# femto.net
KiCad netlist of a schematic drawn in EAGLE
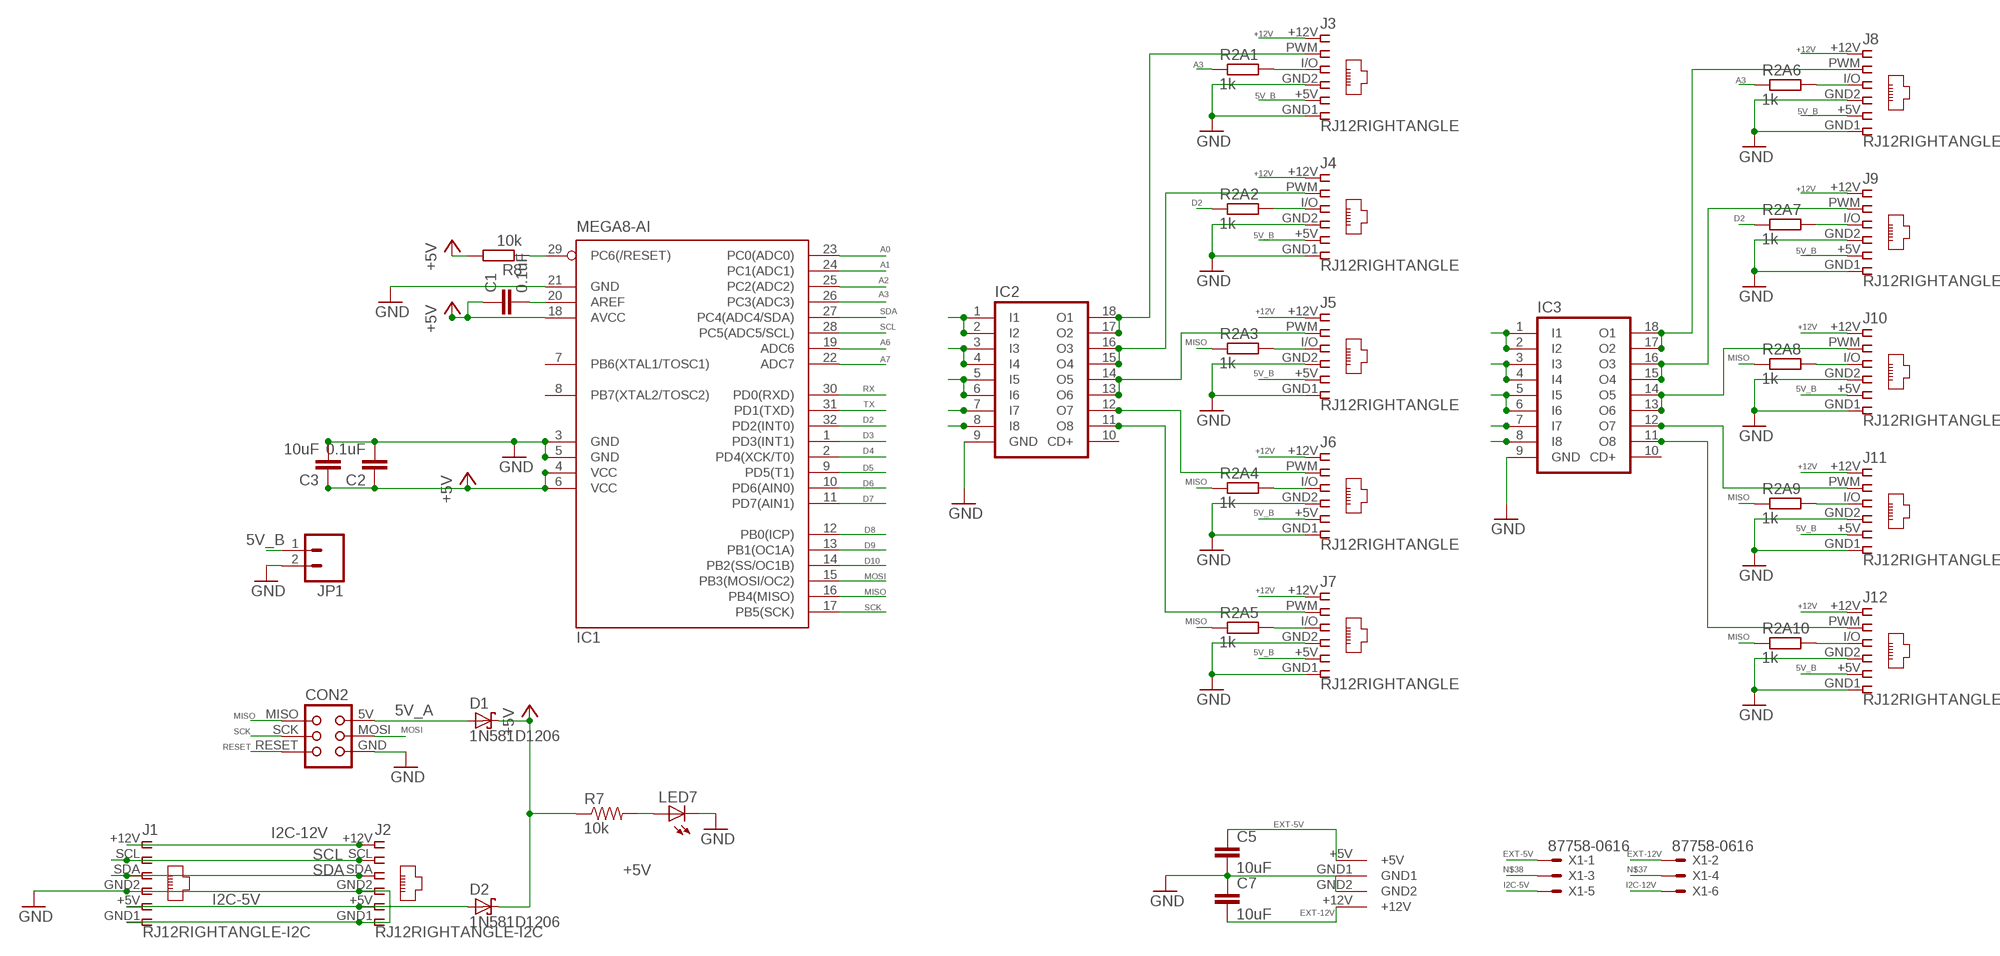
[diagram p0: schematic, sheet 1]

(export (version "E")
  (design (tool "Eeschema 10.0.6"))
  (components
    (comp (ref "C1")
      (value "0.1uF")
      (footprint "eagle-import:C1206")
      (libsource (lib "eagle-import") (part "resistor_C-EUC1206"))
    )
    (comp (ref "C2")
      (value "0.1uF")
      (footprint "eagle-import:C1206")
      (libsource (lib "eagle-import") (part "resistor_C-EUC1206"))
    )
    (comp (ref "C3")
      (value "10uF")
      (footprint "eagle-import:C1206")
      (libsource (lib "eagle-import") (part "resistor_C-EUC1206"))
    )
    (comp (ref "C5")
      (value "10uF")
      (footprint "eagle-import:C1206")
      (libsource (lib "eagle-import") (part "C-EUC1206"))
    )
    (comp (ref "C7")
      (value "10uF")
      (footprint "eagle-import:C1206")
      (libsource (lib "eagle-import") (part "C-EUC1206"))
    )
    (comp (ref "CON2")
      (value "TINYISPTAG")
      (footprint "eagle-import:TC2030-MCP")
      (libsource (lib "eagle-import") (part "TINYISPTAG"))
    )
    (comp (ref "D1")
      (value "1N581D1206")
      (footprint "eagle-import:LED-1206")
      (libsource (lib "eagle-import") (part "1N581D1206"))
    )
    (comp (ref "D2")
      (value "1N581D1206")
      (footprint "eagle-import:LED-1206")
      (libsource (lib "eagle-import") (part "1N581D1206"))
    )
    (comp (ref "IC1")
      (value "MEGA8-AI")
      (footprint "eagle-import:TQFP32-08")
      (fields (field (name "MPN") "ATMEGA8-16AU"))
      (libsource (lib "eagle-import") (part "MEGA8-AI"))
    )
    (comp (ref "IC2")
      (value "ULN2803A")
      (footprint "eagle-import:SO18W")
      (libsource (lib "eagle-import") (part "ULN2803A"))
    )
    (comp (ref "IC3")
      (value "ULN2803A")
      (footprint "eagle-import:SO18W")
      (libsource (lib "eagle-import") (part "ULN2803A"))
    )
    (comp (ref "J1")
      (value "RJ12RIGHTANGLE-I2C")
      (footprint "eagle-import:RJ12-RIGHTANGLE-I2C")
      (libsource (lib "eagle-import") (part "RJ12RIGHTANGLE-I2C"))
    )
    (comp (ref "J2")
      (value "RJ12RIGHTANGLE-I2C")
      (footprint "eagle-import:RJ12-RIGHTANGLE-I2C")
      (libsource (lib "eagle-import") (part "RJ12RIGHTANGLE-I2C"))
    )
    (comp (ref "J3")
      (value "RJ12RIGHTANGLE")
      (footprint "eagle-import:RJ12-RIGHTANGLE")
      (libsource (lib "eagle-import") (part "RJ12RIGHTANGLE"))
    )
    (comp (ref "J4")
      (value "RJ12RIGHTANGLE")
      (footprint "eagle-import:RJ12-RIGHTANGLE")
      (libsource (lib "eagle-import") (part "RJ12RIGHTANGLE"))
    )
    (comp (ref "J5")
      (value "RJ12RIGHTANGLE")
      (footprint "eagle-import:RJ12-RIGHTANGLE")
      (libsource (lib "eagle-import") (part "RJ12RIGHTANGLE"))
    )
    (comp (ref "J6")
      (value "RJ12RIGHTANGLE")
      (footprint "eagle-import:RJ12-RIGHTANGLE")
      (libsource (lib "eagle-import") (part "RJ12RIGHTANGLE"))
    )
    (comp (ref "J7")
      (value "RJ12RIGHTANGLE")
      (footprint "eagle-import:RJ12-RIGHTANGLE")
      (libsource (lib "eagle-import") (part "RJ12RIGHTANGLE"))
    )
    (comp (ref "J8")
      (value "RJ12RIGHTANGLE")
      (footprint "eagle-import:RJ12-RIGHTANGLE")
      (libsource (lib "eagle-import") (part "RJ12RIGHTANGLE"))
    )
    (comp (ref "J9")
      (value "RJ12RIGHTANGLE")
      (footprint "eagle-import:RJ12-RIGHTANGLE")
      (libsource (lib "eagle-import") (part "RJ12RIGHTANGLE"))
    )
    (comp (ref "J10")
      (value "RJ12RIGHTANGLE")
      (footprint "eagle-import:RJ12-RIGHTANGLE")
      (libsource (lib "eagle-import") (part "RJ12RIGHTANGLE"))
    )
    (comp (ref "J11")
      (value "RJ12RIGHTANGLE")
      (footprint "eagle-import:RJ12-RIGHTANGLE")
      (libsource (lib "eagle-import") (part "RJ12RIGHTANGLE"))
    )
    (comp (ref "J12")
      (value "RJ12RIGHTANGLE")
      (footprint "eagle-import:RJ12-RIGHTANGLE")
      (libsource (lib "eagle-import") (part "RJ12RIGHTANGLE"))
    )
    (comp (ref "JP1")
      (value "M023.5MM")
      (footprint "eagle-import:SCREWTERMINAL-3.5MM-2")
      (libsource (lib "eagle-import") (part "M023.5MM"))
    )
    (comp (ref "LED7")
      (value "LEDCHIP-LED0603")
      (footprint "eagle-import:CHIP-LED0603")
      (libsource (lib "eagle-import") (part "LEDCHIP-LED0603"))
    )
    (comp (ref "R2A1")
      (value "1k")
      (footprint "eagle-import:M1206")
      (libsource (lib "eagle-import") (part "R-EU_M1206"))
    )
    (comp (ref "R2A2")
      (value "1k")
      (footprint "eagle-import:M1206")
      (libsource (lib "eagle-import") (part "R-EU_M1206"))
    )
    (comp (ref "R2A3")
      (value "1k")
      (footprint "eagle-import:M1206")
      (libsource (lib "eagle-import") (part "R-EU_M1206"))
    )
    (comp (ref "R2A4")
      (value "1k")
      (footprint "eagle-import:M1206")
      (libsource (lib "eagle-import") (part "R-EU_M1206"))
    )
    (comp (ref "R2A5")
      (value "1k")
      (footprint "eagle-import:M1206")
      (libsource (lib "eagle-import") (part "R-EU_M1206"))
    )
    (comp (ref "R2A6")
      (value "1k")
      (footprint "eagle-import:M1206")
      (libsource (lib "eagle-import") (part "R-EU_M1206"))
    )
    (comp (ref "R2A7")
      (value "1k")
      (footprint "eagle-import:M1206")
      (libsource (lib "eagle-import") (part "R-EU_M1206"))
    )
    (comp (ref "R2A8")
      (value "1k")
      (footprint "eagle-import:M1206")
      (libsource (lib "eagle-import") (part "R-EU_M1206"))
    )
    (comp (ref "R2A9")
      (value "1k")
      (footprint "eagle-import:M1206")
      (libsource (lib "eagle-import") (part "R-EU_M1206"))
    )
    (comp (ref "R2A10")
      (value "1k")
      (footprint "eagle-import:M1206")
      (libsource (lib "eagle-import") (part "R-EU_M1206"))
    )
    (comp (ref "R7")
      (value "10k")
      (footprint "eagle-import:0603-RES")
      (libsource (lib "eagle-import") (part "RESISTOR0603-RES"))
    )
    (comp (ref "R8")
      (value "10k")
      (footprint "eagle-import:M1206")
      (libsource (lib "eagle-import") (part "R-EU_M1206"))
    )
    (comp (ref "U$1")
      (value "KPJX-4S-S")
      (footprint "eagle-import:KPJX-4S-S")
      (libsource (lib "eagle-import") (part "KPJX-4S-S"))
    )
    (comp (ref "X1")
      (value "87758-0616")
      (footprint "eagle-import:87758-0616")
      (libsource (lib "eagle-import") (part "87758-0616"))
    )
  )
  (nets
    (net (code "1") (name "+5V") (class "Default")
      (node (ref "C1") (pin "1") (pinfunction "1_1") (pintype "passive"))
      (node (ref "C2") (pin "1") (pinfunction "1_1") (pintype "passive"))
      (node (ref "C3") (pin "1") (pinfunction "1_1") (pintype "passive"))
      (node (ref "D1") (pin "C") (pinfunction "C_C") (pintype "passive"))
      (node (ref "D2") (pin "C") (pinfunction "C_C") (pintype "passive"))
      (node (ref "IC1") (pin "18") (pinfunction "AVCC_18") (pintype "power_in"))
      (node (ref "IC1") (pin "4") (pinfunction "VCC_4") (pintype "power_in"))
      (node (ref "IC1") (pin "6") (pinfunction "VCC_6") (pintype "power_in"))
      (node (ref "R7") (pin "1") (pinfunction "1_1") (pintype "passive"))
      (node (ref "R8") (pin "2") (pinfunction "2_2") (pintype "passive"))
    )
    (net (code "2") (name "/+12V") (class "Default")
      (node (ref "J10") (pin "+12V") (pinfunction "1_+12V") (pintype "bidirectional"))
      (node (ref "J11") (pin "+12V") (pinfunction "1_+12V") (pintype "bidirectional"))
      (node (ref "J12") (pin "+12V") (pinfunction "1_+12V") (pintype "bidirectional"))
      (node (ref "J3") (pin "+12V") (pinfunction "1_+12V") (pintype "bidirectional"))
      (node (ref "J4") (pin "+12V") (pinfunction "1_+12V") (pintype "bidirectional"))
      (node (ref "J5") (pin "+12V") (pinfunction "1_+12V") (pintype "bidirectional"))
      (node (ref "J6") (pin "+12V") (pinfunction "1_+12V") (pintype "bidirectional"))
      (node (ref "J7") (pin "+12V") (pinfunction "1_+12V") (pintype "bidirectional"))
      (node (ref "J8") (pin "+12V") (pinfunction "1_+12V") (pintype "bidirectional"))
      (node (ref "J9") (pin "+12V") (pinfunction "1_+12V") (pintype "bidirectional"))
    )
    (net (code "3") (name "/5V_A") (class "Default")
      (node (ref "CON2") (pin "5V") (pinfunction "VCC_5V") (pintype "passive"))
      (node (ref "D1") (pin "A") (pinfunction "A_A") (pintype "passive"))
    )
    (net (code "4") (name "/5V_B") (class "Default")
      (node (ref "J10") (pin "+5V") (pinfunction "5_+5V") (pintype "bidirectional"))
      (node (ref "J11") (pin "+5V") (pinfunction "5_+5V") (pintype "bidirectional"))
      (node (ref "J12") (pin "+5V") (pinfunction "5_+5V") (pintype "bidirectional"))
      (node (ref "J3") (pin "+5V") (pinfunction "5_+5V") (pintype "bidirectional"))
      (node (ref "J4") (pin "+5V") (pinfunction "5_+5V") (pintype "bidirectional"))
      (node (ref "J5") (pin "+5V") (pinfunction "5_+5V") (pintype "bidirectional"))
      (node (ref "J6") (pin "+5V") (pinfunction "5_+5V") (pintype "bidirectional"))
      (node (ref "J7") (pin "+5V") (pinfunction "5_+5V") (pintype "bidirectional"))
      (node (ref "J8") (pin "+5V") (pinfunction "5_+5V") (pintype "bidirectional"))
      (node (ref "J9") (pin "+5V") (pinfunction "5_+5V") (pintype "bidirectional"))
      (node (ref "JP1") (pin "1") (pinfunction "1_1") (pintype "passive"))
    )
    (net (code "5") (name "/A0") (class "Default")
      (node (ref "IC1") (pin "23") (pinfunction "PC0(ADC0)_23") (pintype "bidirectional"))
    )
    (net (code "6") (name "/A1") (class "Default")
      (node (ref "IC1") (pin "24") (pinfunction "PC1(ADC1)_24") (pintype "bidirectional"))
    )
    (net (code "7") (name "/A2") (class "Default")
      (node (ref "IC1") (pin "25") (pinfunction "PC2(ADC2)_25") (pintype "bidirectional"))
    )
    (net (code "8") (name "/A3") (class "Default")
      (node (ref "IC1") (pin "26") (pinfunction "PC3(ADC3)_26") (pintype "bidirectional"))
      (node (ref "R2A1") (pin "1") (pinfunction "1_1") (pintype "passive"))
      (node (ref "R2A6") (pin "1") (pinfunction "1_1") (pintype "passive"))
    )
    (net (code "9") (name "/A6") (class "Default")
      (node (ref "IC1") (pin "19") (pinfunction "ADC6_19") (pintype "bidirectional"))
    )
    (net (code "10") (name "/A7") (class "Default")
      (node (ref "IC1") (pin "22") (pinfunction "ADC7_22") (pintype "bidirectional"))
    )
    (net (code "11") (name "/D2") (class "Default")
      (node (ref "IC1") (pin "32") (pinfunction "PD2(INT0)_32") (pintype "bidirectional"))
      (node (ref "R2A2") (pin "1") (pinfunction "1_1") (pintype "passive"))
      (node (ref "R2A7") (pin "1") (pinfunction "1_1") (pintype "passive"))
    )
    (net (code "12") (name "/D3") (class "Default")
      (node (ref "IC1") (pin "1") (pinfunction "PD3(INT1)_1") (pintype "bidirectional"))
    )
    (net (code "13") (name "/D4") (class "Default")
      (node (ref "IC1") (pin "2") (pinfunction "PD4(XCK/T0)_2") (pintype "bidirectional"))
    )
    (net (code "14") (name "/D5") (class "Default")
      (node (ref "IC1") (pin "9") (pinfunction "PD5(T1)_9") (pintype "bidirectional"))
    )
    (net (code "15") (name "/D6") (class "Default")
      (node (ref "IC1") (pin "10") (pinfunction "PD6(AIN0)_10") (pintype "bidirectional"))
    )
    (net (code "16") (name "/D7") (class "Default")
      (node (ref "IC1") (pin "11") (pinfunction "PD7(AIN1)_11") (pintype "bidirectional"))
    )
    (net (code "17") (name "/D8") (class "Default")
      (node (ref "IC1") (pin "12") (pinfunction "PB0(ICP)_12") (pintype "bidirectional"))
    )
    (net (code "18") (name "/D9") (class "Default")
      (node (ref "IC1") (pin "13") (pinfunction "PB1(OC1A)_13") (pintype "bidirectional"))
    )
    (net (code "19") (name "/D10") (class "Default")
      (node (ref "IC1") (pin "14") (pinfunction "PB2(SS/OC1B)_14") (pintype "bidirectional"))
    )
    (net (code "20") (name "/EXT-5V") (class "Default")
      (node (ref "C5") (pin "1") (pinfunction "1_1") (pintype "passive"))
      (node (ref "U$1") (pin "+5V") (pinfunction "+5V_+5V") (pintype "power_in"))
      (node (ref "X1") (pin "1") (pinfunction "S_1") (pintype "passive"))
    )
    (net (code "21") (name "/EXT-12V") (class "Default")
      (node (ref "C7") (pin "2") (pinfunction "2_2") (pintype "passive"))
      (node (ref "U$1") (pin "+12V") (pinfunction "+12V_+12V") (pintype "power_in"))
      (node (ref "X1") (pin "2") (pinfunction "S_2") (pintype "passive"))
    )
    (net (code "22") (name "/I2C-5V") (class "Default")
      (node (ref "D2") (pin "A") (pinfunction "A_A") (pintype "passive"))
      (node (ref "J1") (pin "+5V") (pinfunction "5_+5V") (pintype "bidirectional"))
      (node (ref "J2") (pin "+5V") (pinfunction "5_+5V") (pintype "bidirectional"))
      (node (ref "X1") (pin "5") (pinfunction "S_5") (pintype "passive"))
    )
    (net (code "23") (name "/I2C-12V") (class "Default")
      (node (ref "J1") (pin "+12V") (pinfunction "1_+12V") (pintype "bidirectional"))
      (node (ref "J2") (pin "+12V") (pinfunction "1_+12V") (pintype "bidirectional"))
      (node (ref "X1") (pin "6") (pinfunction "S_6") (pintype "passive"))
    )
    (net (code "24") (name "/MISO") (class "Default")
      (node (ref "CON2") (pin "MISO") (pinfunction "MISO_MISO") (pintype "passive"))
      (node (ref "IC1") (pin "16") (pinfunction "PB4(MISO)_16") (pintype "bidirectional"))
      (node (ref "R2A10") (pin "1") (pinfunction "1_1") (pintype "passive"))
      (node (ref "R2A3") (pin "1") (pinfunction "1_1") (pintype "passive"))
      (node (ref "R2A4") (pin "1") (pinfunction "1_1") (pintype "passive"))
      (node (ref "R2A5") (pin "1") (pinfunction "1_1") (pintype "passive"))
      (node (ref "R2A8") (pin "1") (pinfunction "1_1") (pintype "passive"))
      (node (ref "R2A9") (pin "1") (pinfunction "1_1") (pintype "passive"))
    )
    (net (code "25") (name "/MOSI") (class "Default")
      (node (ref "CON2") (pin "MOSI") (pinfunction "MOSI_MOSI") (pintype "passive"))
      (node (ref "IC1") (pin "15") (pinfunction "PB3(MOSI/OC2)_15") (pintype "bidirectional"))
    )
    (net (code "26") (name "/N$37") (class "Default")
      (node (ref "X1") (pin "4") (pinfunction "S_4") (pintype "passive"))
    )
    (net (code "27") (name "/N$38") (class "Default")
      (node (ref "X1") (pin "3") (pinfunction "S_3") (pintype "passive"))
    )
    (net (code "28") (name "/RESET") (class "Default")
      (node (ref "CON2") (pin "RESET") (pinfunction "RESET_RESET") (pintype "passive"))
      (node (ref "IC1") (pin "29") (pinfunction "PC6(/RESET)_29") (pintype "bidirectional"))
      (node (ref "R8") (pin "1") (pinfunction "1_1") (pintype "passive"))
    )
    (net (code "29") (name "/RX") (class "Default")
      (node (ref "IC1") (pin "30") (pinfunction "PD0(RXD)_30") (pintype "bidirectional"))
    )
    (net (code "30") (name "/SCK") (class "Default")
      (node (ref "CON2") (pin "SCK") (pinfunction "SCK_SCK") (pintype "passive"))
      (node (ref "IC1") (pin "17") (pinfunction "PB5(SCK)_17") (pintype "bidirectional"))
    )
    (net (code "31") (name "/SCL") (class "Default")
      (node (ref "IC1") (pin "28") (pinfunction "PC5(ADC5/SCL)_28") (pintype "bidirectional"))
      (node (ref "J1") (pin "SCL") (pinfunction "2_SCL") (pintype "bidirectional"))
      (node (ref "J2") (pin "SCL") (pinfunction "2_SCL") (pintype "bidirectional"))
    )
    (net (code "32") (name "/SDA") (class "Default")
      (node (ref "IC1") (pin "27") (pinfunction "PC4(ADC4/SDA)_27") (pintype "bidirectional"))
      (node (ref "J1") (pin "SDA") (pinfunction "3_SDA") (pintype "bidirectional"))
      (node (ref "J2") (pin "SDA") (pinfunction "3_SDA") (pintype "bidirectional"))
    )
    (net (code "33") (name "/TX") (class "Default")
      (node (ref "IC1") (pin "31") (pinfunction "PD1(TXD)_31") (pintype "bidirectional"))
    )
    (net (code "34") (name "GND") (class "Default")
      (node (ref "C2") (pin "2") (pinfunction "2_2") (pintype "passive"))
      (node (ref "C3") (pin "2") (pinfunction "2_2") (pintype "passive"))
      (node (ref "C5") (pin "2") (pinfunction "2_2") (pintype "passive"))
      (node (ref "C7") (pin "1") (pinfunction "1_1") (pintype "passive"))
      (node (ref "CON2") (pin "GND") (pinfunction "GND_GND") (pintype "passive"))
      (node (ref "IC1") (pin "21") (pinfunction "GND_21") (pintype "power_in"))
      (node (ref "IC1") (pin "3") (pinfunction "GND_3") (pintype "power_in"))
      (node (ref "IC1") (pin "5") (pinfunction "GND_5") (pintype "power_in"))
      (node (ref "IC2") (pin "9") (pinfunction "GND_9") (pintype "power_in"))
      (node (ref "IC3") (pin "9") (pinfunction "GND_9") (pintype "power_in"))
      (node (ref "J1") (pin "GND1") (pinfunction "6_GND1") (pintype "bidirectional"))
      (node (ref "J1") (pin "GND2") (pinfunction "4_GND2") (pintype "bidirectional"))
      (node (ref "J10") (pin "GND1") (pinfunction "6_GND1") (pintype "bidirectional"))
      (node (ref "J10") (pin "GND2") (pinfunction "4_GND2") (pintype "bidirectional"))
      (node (ref "J11") (pin "GND1") (pinfunction "6_GND1") (pintype "bidirectional"))
      (node (ref "J11") (pin "GND2") (pinfunction "4_GND2") (pintype "bidirectional"))
      (node (ref "J12") (pin "GND1") (pinfunction "6_GND1") (pintype "bidirectional"))
      (node (ref "J12") (pin "GND2") (pinfunction "4_GND2") (pintype "bidirectional"))
      (node (ref "J2") (pin "GND1") (pinfunction "6_GND1") (pintype "bidirectional"))
      (node (ref "J2") (pin "GND2") (pinfunction "4_GND2") (pintype "bidirectional"))
      (node (ref "J3") (pin "GND1") (pinfunction "6_GND1") (pintype "bidirectional"))
      (node (ref "J3") (pin "GND2") (pinfunction "4_GND2") (pintype "bidirectional"))
      (node (ref "J4") (pin "GND1") (pinfunction "6_GND1") (pintype "bidirectional"))
      (node (ref "J4") (pin "GND2") (pinfunction "4_GND2") (pintype "bidirectional"))
      (node (ref "J5") (pin "GND1") (pinfunction "6_GND1") (pintype "bidirectional"))
      (node (ref "J5") (pin "GND2") (pinfunction "4_GND2") (pintype "bidirectional"))
      (node (ref "J6") (pin "GND1") (pinfunction "6_GND1") (pintype "bidirectional"))
      (node (ref "J6") (pin "GND2") (pinfunction "4_GND2") (pintype "bidirectional"))
      (node (ref "J7") (pin "GND1") (pinfunction "6_GND1") (pintype "bidirectional"))
      (node (ref "J7") (pin "GND2") (pinfunction "4_GND2") (pintype "bidirectional"))
      (node (ref "J8") (pin "GND1") (pinfunction "6_GND1") (pintype "bidirectional"))
      (node (ref "J8") (pin "GND2") (pinfunction "4_GND2") (pintype "bidirectional"))
      (node (ref "J9") (pin "GND1") (pinfunction "6_GND1") (pintype "bidirectional"))
      (node (ref "J9") (pin "GND2") (pinfunction "4_GND2") (pintype "bidirectional"))
      (node (ref "JP1") (pin "2") (pinfunction "2_2") (pintype "passive"))
      (node (ref "LED7") (pin "C") (pinfunction "C_C") (pintype "passive"))
      (node (ref "U$1") (pin "GND1") (pinfunction "GND1_GND1") (pintype "input"))
      (node (ref "U$1") (pin "GND2") (pinfunction "GND2_GND2") (pintype "input"))
    )
    (net (code "35") (name "Net-(IC1-AREF)") (class "Default")
      (node (ref "C1") (pin "2") (pinfunction "2_2") (pintype "passive"))
      (node (ref "IC1") (pin "20") (pinfunction "AREF_20") (pintype "passive"))
    )
    (net (code "36") (name "Net-(IC2-I1)") (class "Default")
      (node (ref "IC2") (pin "1") (pinfunction "I1_1") (pintype "input"))
      (node (ref "IC2") (pin "2") (pinfunction "I2_2") (pintype "input"))
    )
    (net (code "37") (name "Net-(IC2-I3)") (class "Default")
      (node (ref "IC2") (pin "3") (pinfunction "I3_3") (pintype "input"))
      (node (ref "IC2") (pin "4") (pinfunction "I4_4") (pintype "input"))
    )
    (net (code "38") (name "Net-(IC2-I5)") (class "Default")
      (node (ref "IC2") (pin "5") (pinfunction "I5_5") (pintype "input"))
      (node (ref "IC2") (pin "6") (pinfunction "I6_6") (pintype "input"))
    )
    (net (code "39") (name "Net-(IC2-O1)") (class "Default")
      (node (ref "IC2") (pin "17") (pinfunction "O2_17") (pintype "open_collector"))
      (node (ref "IC2") (pin "18") (pinfunction "O1_18") (pintype "open_collector"))
      (node (ref "J3") (pin "PWM") (pinfunction "2_PWM") (pintype "bidirectional"))
    )
    (net (code "40") (name "Net-(IC2-O3)") (class "Default")
      (node (ref "IC2") (pin "15") (pinfunction "O4_15") (pintype "open_collector"))
      (node (ref "IC2") (pin "16") (pinfunction "O3_16") (pintype "open_collector"))
      (node (ref "J4") (pin "PWM") (pinfunction "2_PWM") (pintype "bidirectional"))
    )
    (net (code "41") (name "Net-(IC2-O5)") (class "Default")
      (node (ref "IC2") (pin "13") (pinfunction "O6_13") (pintype "open_collector"))
      (node (ref "IC2") (pin "14") (pinfunction "O5_14") (pintype "open_collector"))
      (node (ref "J5") (pin "PWM") (pinfunction "2_PWM") (pintype "bidirectional"))
    )
    (net (code "42") (name "Net-(IC2-O7)") (class "Default")
      (node (ref "IC2") (pin "12") (pinfunction "O7_12") (pintype "open_collector"))
      (node (ref "J6") (pin "PWM") (pinfunction "2_PWM") (pintype "bidirectional"))
    )
    (net (code "43") (name "Net-(IC2-O8)") (class "Default")
      (node (ref "IC2") (pin "11") (pinfunction "O8_11") (pintype "open_collector"))
      (node (ref "J7") (pin "PWM") (pinfunction "2_PWM") (pintype "bidirectional"))
    )
    (net (code "44") (name "Net-(IC3-I1)") (class "Default")
      (node (ref "IC3") (pin "1") (pinfunction "I1_1") (pintype "input"))
      (node (ref "IC3") (pin "2") (pinfunction "I2_2") (pintype "input"))
    )
    (net (code "45") (name "Net-(IC3-I3)") (class "Default")
      (node (ref "IC3") (pin "3") (pinfunction "I3_3") (pintype "input"))
      (node (ref "IC3") (pin "4") (pinfunction "I4_4") (pintype "input"))
    )
    (net (code "46") (name "Net-(IC3-I5)") (class "Default")
      (node (ref "IC3") (pin "5") (pinfunction "I5_5") (pintype "input"))
      (node (ref "IC3") (pin "6") (pinfunction "I6_6") (pintype "input"))
    )
    (net (code "47") (name "Net-(IC3-O1)") (class "Default")
      (node (ref "IC3") (pin "17") (pinfunction "O2_17") (pintype "open_collector"))
      (node (ref "IC3") (pin "18") (pinfunction "O1_18") (pintype "open_collector"))
      (node (ref "J8") (pin "PWM") (pinfunction "2_PWM") (pintype "bidirectional"))
    )
    (net (code "48") (name "Net-(IC3-O3)") (class "Default")
      (node (ref "IC3") (pin "15") (pinfunction "O4_15") (pintype "open_collector"))
      (node (ref "IC3") (pin "16") (pinfunction "O3_16") (pintype "open_collector"))
      (node (ref "J9") (pin "PWM") (pinfunction "2_PWM") (pintype "bidirectional"))
    )
    (net (code "49") (name "Net-(IC3-O5)") (class "Default")
      (node (ref "IC3") (pin "13") (pinfunction "O6_13") (pintype "open_collector"))
      (node (ref "IC3") (pin "14") (pinfunction "O5_14") (pintype "open_collector"))
      (node (ref "J10") (pin "PWM") (pinfunction "2_PWM") (pintype "bidirectional"))
    )
    (net (code "50") (name "Net-(IC3-O7)") (class "Default")
      (node (ref "IC3") (pin "12") (pinfunction "O7_12") (pintype "open_collector"))
      (node (ref "J11") (pin "PWM") (pinfunction "2_PWM") (pintype "bidirectional"))
    )
    (net (code "51") (name "Net-(IC3-O8)") (class "Default")
      (node (ref "IC3") (pin "11") (pinfunction "O8_11") (pintype "open_collector"))
      (node (ref "J12") (pin "PWM") (pinfunction "2_PWM") (pintype "bidirectional"))
    )
    (net (code "52") (name "Net-(J3-3)") (class "Default")
      (node (ref "J3") (pin "I/O") (pinfunction "3_I/O") (pintype "bidirectional"))
      (node (ref "R2A1") (pin "2") (pinfunction "2_2") (pintype "passive"))
    )
    (net (code "53") (name "Net-(J4-3)") (class "Default")
      (node (ref "J4") (pin "I/O") (pinfunction "3_I/O") (pintype "bidirectional"))
      (node (ref "R2A2") (pin "2") (pinfunction "2_2") (pintype "passive"))
    )
    (net (code "54") (name "Net-(J5-3)") (class "Default")
      (node (ref "J5") (pin "I/O") (pinfunction "3_I/O") (pintype "bidirectional"))
      (node (ref "R2A3") (pin "2") (pinfunction "2_2") (pintype "passive"))
    )
    (net (code "55") (name "Net-(J6-3)") (class "Default")
      (node (ref "J6") (pin "I/O") (pinfunction "3_I/O") (pintype "bidirectional"))
      (node (ref "R2A4") (pin "2") (pinfunction "2_2") (pintype "passive"))
    )
    (net (code "56") (name "Net-(J7-3)") (class "Default")
      (node (ref "J7") (pin "I/O") (pinfunction "3_I/O") (pintype "bidirectional"))
      (node (ref "R2A5") (pin "2") (pinfunction "2_2") (pintype "passive"))
    )
    (net (code "57") (name "Net-(J8-3)") (class "Default")
      (node (ref "J8") (pin "I/O") (pinfunction "3_I/O") (pintype "bidirectional"))
      (node (ref "R2A6") (pin "2") (pinfunction "2_2") (pintype "passive"))
    )
    (net (code "58") (name "Net-(J9-3)") (class "Default")
      (node (ref "J9") (pin "I/O") (pinfunction "3_I/O") (pintype "bidirectional"))
      (node (ref "R2A7") (pin "2") (pinfunction "2_2") (pintype "passive"))
    )
    (net (code "59") (name "Net-(J10-3)") (class "Default")
      (node (ref "J10") (pin "I/O") (pinfunction "3_I/O") (pintype "bidirectional"))
      (node (ref "R2A8") (pin "2") (pinfunction "2_2") (pintype "passive"))
    )
    (net (code "60") (name "Net-(J11-3)") (class "Default")
      (node (ref "J11") (pin "I/O") (pinfunction "3_I/O") (pintype "bidirectional"))
      (node (ref "R2A9") (pin "2") (pinfunction "2_2") (pintype "passive"))
    )
    (net (code "61") (name "Net-(J12-3)") (class "Default")
      (node (ref "J12") (pin "I/O") (pinfunction "3_I/O") (pintype "bidirectional"))
      (node (ref "R2A10") (pin "2") (pinfunction "2_2") (pintype "passive"))
    )
    (net (code "62") (name "Net-(LED7-PadA)") (class "Default")
      (node (ref "LED7") (pin "A") (pinfunction "A_A") (pintype "passive"))
      (node (ref "R7") (pin "2") (pinfunction "2_2") (pintype "passive"))
    )
    (net (code "63") (name "unconnected-(IC1-PB6(XTAL1{slash}TOSC1)-Pad7)") (class "Default")
      (node (ref "IC1") (pin "7") (pinfunction "PB6(XTAL1/TOSC1)_7") (pintype "bidirectional"))
    )
    (net (code "64") (name "unconnected-(IC1-PB7(XTAL2{slash}TOSC2)-Pad8)") (class "Default")
      (node (ref "IC1") (pin "8") (pinfunction "PB7(XTAL2/TOSC2)_8") (pintype "bidirectional"))
    )
    (net (code "65") (name "unconnected-(IC2-CD+-Pad10)") (class "Default")
      (node (ref "IC2") (pin "10") (pinfunction "CD+_10") (pintype "passive"))
    )
    (net (code "66") (name "unconnected-(IC2-I7-Pad7)") (class "Default")
      (node (ref "IC2") (pin "7") (pinfunction "I7_7") (pintype "input"))
    )
    (net (code "67") (name "unconnected-(IC2-I8-Pad8)") (class "Default")
      (node (ref "IC2") (pin "8") (pinfunction "I8_8") (pintype "input"))
    )
    (net (code "68") (name "unconnected-(IC3-CD+-Pad10)") (class "Default")
      (node (ref "IC3") (pin "10") (pinfunction "CD+_10") (pintype "passive"))
    )
    (net (code "69") (name "unconnected-(IC3-I7-Pad7)") (class "Default")
      (node (ref "IC3") (pin "7") (pinfunction "I7_7") (pintype "input"))
    )
    (net (code "70") (name "unconnected-(IC3-I8-Pad8)") (class "Default")
      (node (ref "IC3") (pin "8") (pinfunction "I8_8") (pintype "input"))
    )
  )
)
